# ProPrj_PCB.net
KiCad netlist of a schematic drawn in EasyEDA Pro
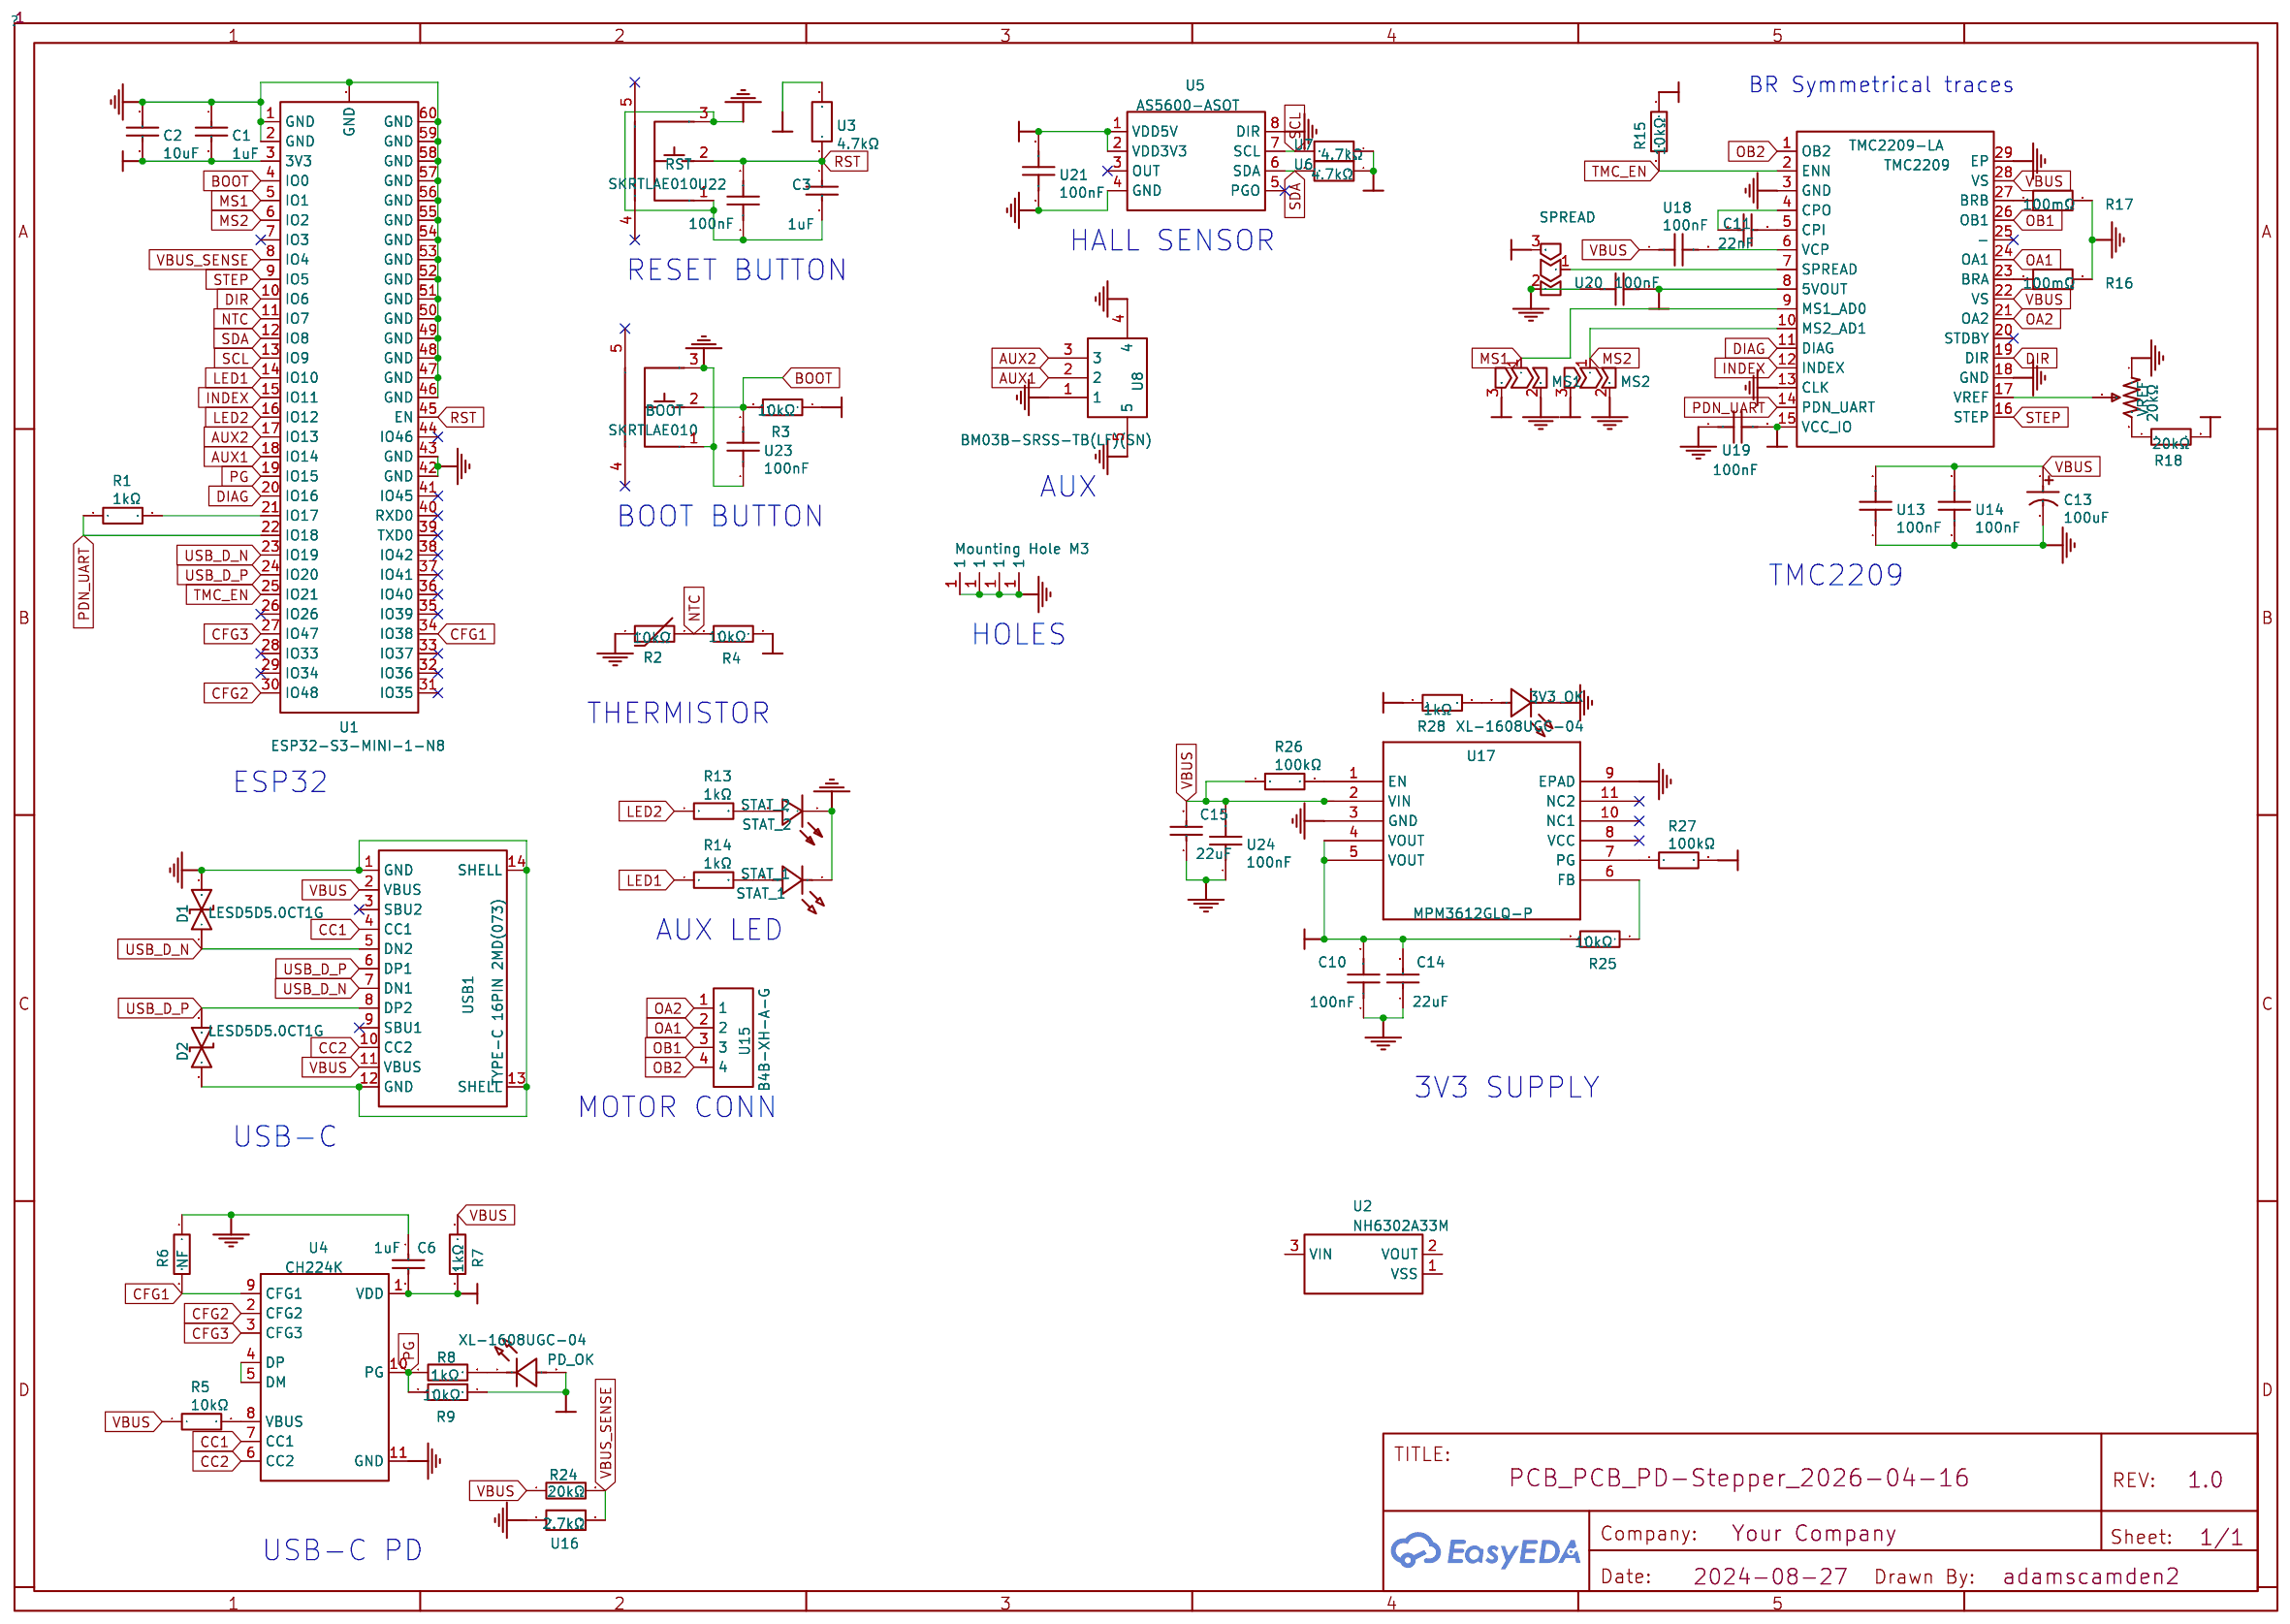
[diagram p0: schematic sheet]

(export (version "E")
  (design (tool "Eeschema 10.0.6"))
  (components
    (comp (ref "3V3_OK")
      (value "XL-1608UGC-04")
      (footprint "easyedapro:LED0603-RD_GREEN")
      (fields (field (name "Manufacturer") "XINGLIGHT(成兴光)") (field (name "Contributor") "lcsc"))
      (libsource (lib "") (part "XL-1608UGC-04_1"))
    )
    (comp (ref "BOOT")
      (value "SKRTLAE010")
      (footprint "easyedapro:KEY-SMD_SKRTLAE010")
      (fields (field (name "Manufacturer") "ALPSALPINE(阿尔卑斯阿尔派)"))
      (libsource (lib "easyedapro") (part "SKRTLAE010"))
    )
    (comp (ref "C1")
      (value "1uF")
      (footprint "easyedapro:C0402")
      (fields (field (name "Manufacturer Part") "0402B102K500NT") (field (name "Manufacturer") "FH(风华)"))
      (libsource (lib "easyedapro") (part "1uF"))
    )
    (comp (ref "C2")
      (value "10uF")
      (footprint "easyedapro:C0402")
      (fields (field (name "Manufacturer Part") "0402B102K500NT") (field (name "Manufacturer") "FH(风华)"))
      (libsource (lib "easyedapro") (part "10uF"))
    )
    (comp (ref "C3")
      (value "1uF")
      (footprint "easyedapro:C0402")
      (fields (field (name "Manufacturer Part") "0402B102K500NT") (field (name "Manufacturer") "FH(风华)"))
      (libsource (lib "easyedapro") (part "1uF"))
    )
    (comp (ref "C6")
      (value "1uF")
      (footprint "easyedapro:C0402")
      (fields (field (name "Manufacturer Part") "0402B102K500NT") (field (name "Manufacturer") "FH(风华)"))
      (libsource (lib "easyedapro") (part "1uF"))
    )
    (comp (ref "C10")
      (value "100nF")
      (footprint "easyedapro:C0402")
      (fields
        (field (name "Manufacturer Part") "CL05B104KO5NNNC")
        (field (name "Manufacturer") "SAMSUNG(三星)")
      )
      (libsource (lib "easyedapro") (part "100nF"))
    )
    (comp (ref "C11")
      (value "22nF")
      (footprint "easyedapro:C0805")
      (fields
        (field (name "Manufacturer Part") "CL21B223KBANNNC")
        (field (name "Manufacturer") "SAMSUNG(三星)")
      )
      (libsource (lib "easyedapro") (part "22nF"))
    )
    (comp (ref "C13")
      (value "100uF")
      (footprint "easyedapro:CAP-SMD_BD6.3-L6.6-W6.6-LS7.6-FD")
      (fields (field (name "Manufacturer Part") "RVT1V101M0607") (field (name "Manufacturer") "ROQANG(容强)"))
      (libsource (lib "easyedapro") (part "100uF"))
    )
    (comp (ref "C14")
      (value "22uF")
      (footprint "easyedapro:C0805")
      (fields (field (name "Manufacturer Part") "0805X226M250NT") (field (name "Manufacturer") "FH(风华)"))
      (libsource (lib "easyedapro") (part "22uF"))
    )
    (comp (ref "C15")
      (value "22uF")
      (footprint "easyedapro:C0805")
      (fields (field (name "Manufacturer Part") "0805X226M250NT") (field (name "Manufacturer") "FH(风华)"))
      (libsource (lib "easyedapro") (part "22uF"))
    )
    (comp (ref "D1")
      (value "LESD5D5.0CT1G")
      (footprint "easyedapro:SOD-523_L1.2-W0.8-LS1.6-BI")
      (fields (field (name "Manufacturer") "LRC(乐山无线电)") (field (name "Contributor") "LCSC"))
      (libsource (lib "easyedapro") (part "LESD5D5.0CT1G"))
    )
    (comp (ref "D2")
      (value "LESD5D5.0CT1G")
      (footprint "easyedapro:SOD-523_L1.2-W0.8-LS1.6-BI")
      (fields (field (name "Manufacturer") "LRC(乐山无线电)") (field (name "Contributor") "LCSC"))
      (libsource (lib "easyedapro") (part "LESD5D5.0CT1G"))
    )
    (comp (ref "MH1")
      (value "Mounting Hole M3")
      (footprint "easyedapro:MOUNTING HOLE M3")
      (fields (field (name "Contributor") "rexsell"))
      (libsource (lib "easyedapro") (part "Mounting Hole M3"))
    )
    (comp (ref "MH2")
      (value "Mounting Hole M3")
      (footprint "easyedapro:MOUNTING HOLE M3")
      (fields (field (name "Contributor") "rexsell"))
      (libsource (lib "easyedapro") (part "Mounting Hole M3"))
    )
    (comp (ref "MH3")
      (value "Mounting Hole M3")
      (footprint "easyedapro:MOUNTING HOLE M3")
      (fields (field (name "Contributor") "rexsell"))
      (libsource (lib "easyedapro") (part "Mounting Hole M3"))
    )
    (comp (ref "MH4")
      (value "Mounting Hole M3")
      (footprint "easyedapro:MOUNTING HOLE M3")
      (fields (field (name "Contributor") "rexsell"))
      (libsource (lib "easyedapro") (part "Mounting Hole M3"))
    )
    (comp (ref "MS1")
      (value "ms1")
      (footprint "easyedapro:SOLDERJUMPER3")
      (fields (field (name "Contributor") "un1tz3r0"))
      (libsource (lib "easyedapro") (part "ms1"))
    )
    (comp (ref "MS2")
      (value "MS2")
      (footprint "easyedapro:SOLDERJUMPER3")
      (fields (field (name "Contributor") "un1tz3r0"))
      (libsource (lib "easyedapro") (part "MS2"))
    )
    (comp (ref "PD_OK")
      (value "XL-1608UGC-04")
      (footprint "easyedapro:LED0603-RD_GREEN")
      (fields (field (name "Manufacturer") "XINGLIGHT(成兴光)") (field (name "Contributor") "lcsc"))
      (libsource (lib "easyedapro") (part "XL-1608UGC-04"))
    )
    (comp (ref "R1")
      (value "1kΩ")
      (footprint "easyedapro:R0402")
      (fields
        (field (name "Manufacturer Part") "0402WGF1001TCE")
        (field (name "Manufacturer") "UNI-ROYAL(厚声)")
      )
      (libsource (lib "easyedapro") (part "1kΩ"))
    )
    (comp (ref "R2")
      (value "10kΩ")
      (footprint "easyedapro:R0402")
      (fields (field (name "Manufacturer Part") "NTCG104BH103JT1") (field (name "Manufacturer") "TDK"))
      (libsource (lib "") (part "10kΩ_1"))
    )
    (comp (ref "R3")
      (value "10kΩ")
      (footprint "easyedapro:R0402")
      (fields
        (field (name "Manufacturer Part") "0402WGF1002TCE")
        (field (name "Manufacturer") "UNI-ROYAL(厚声)")
      )
      (libsource (lib "") (part "10kΩ_2"))
    )
    (comp (ref "R4")
      (value "10kΩ")
      (footprint "easyedapro:R0402")
      (fields
        (field (name "Manufacturer Part") "0402WGF1002TCE")
        (field (name "Manufacturer") "UNI-ROYAL(厚声)")
      )
      (libsource (lib "") (part "10kΩ_2"))
    )
    (comp (ref "R5")
      (value "10kΩ")
      (footprint "easyedapro:R0402")
      (fields
        (field (name "Manufacturer Part") "0402WGF1002TCE")
        (field (name "Manufacturer") "UNI-ROYAL(厚声)")
      )
      (libsource (lib "easyedapro") (part "10kΩ"))
    )
    (comp (ref "R6") (value "NF") (footprint "easyedapro:R0402") (libsource (lib "easyedapro") (part "NF")))
    (comp (ref "R7")
      (value "1kΩ")
      (footprint "easyedapro:R0402")
      (fields
        (field (name "Manufacturer Part") "0402WGF1001TCE")
        (field (name "Manufacturer") "UNI-ROYAL(厚声)")
      )
      (libsource (lib "") (part "1kΩ_1"))
    )
    (comp (ref "R8")
      (value "1kΩ")
      (footprint "easyedapro:R0402")
      (fields
        (field (name "Manufacturer Part") "0402WGF1001TCE")
        (field (name "Manufacturer") "UNI-ROYAL(厚声)")
      )
      (libsource (lib "easyedapro") (part "1kΩ"))
    )
    (comp (ref "R9")
      (value "10kΩ")
      (footprint "easyedapro:R0402")
      (fields
        (field (name "Manufacturer Part") "0402WGF1002TCE")
        (field (name "Manufacturer") "UNI-ROYAL(厚声)")
      )
      (libsource (lib "") (part "10kΩ_2"))
    )
    (comp (ref "R13")
      (value "1kΩ")
      (footprint "easyedapro:R0402")
      (fields
        (field (name "Manufacturer Part") "0402WGF1001TCE")
        (field (name "Manufacturer") "UNI-ROYAL(厚声)")
      )
      (libsource (lib "easyedapro") (part "1kΩ"))
    )
    (comp (ref "R14")
      (value "1kΩ")
      (footprint "easyedapro:R0402")
      (fields
        (field (name "Manufacturer Part") "0402WGF1001TCE")
        (field (name "Manufacturer") "UNI-ROYAL(厚声)")
      )
      (libsource (lib "easyedapro") (part "1kΩ"))
    )
    (comp (ref "R15")
      (value "10kΩ")
      (footprint "easyedapro:R0402")
      (fields
        (field (name "Manufacturer Part") "0402WGF1002TCE")
        (field (name "Manufacturer") "UNI-ROYAL(厚声)")
      )
      (libsource (lib "") (part "10kΩ_3"))
    )
    (comp (ref "R16")
      (value "100mΩ")
      (footprint "easyedapro:R2010")
      (fields
        (field (name "Manufacturer Part") "201007F100LT4E")
        (field (name "Manufacturer") "UNI-ROYAL(厚声)")
        (field (name "Contributor") "LCSC")
      )
      (libsource (lib "easyedapro") (part "100mΩ"))
    )
    (comp (ref "R17")
      (value "100mΩ")
      (footprint "easyedapro:R2010")
      (fields
        (field (name "Manufacturer Part") "201007F100LT4E")
        (field (name "Manufacturer") "UNI-ROYAL(厚声)")
        (field (name "Contributor") "LCSC")
      )
      (libsource (lib "easyedapro") (part "100mΩ"))
    )
    (comp (ref "R18")
      (value "20kΩ")
      (footprint "easyedapro:R0402")
      (fields
        (field (name "Manufacturer Part") "0402WGF2002TCE")
        (field (name "Manufacturer") "UNI-ROYAL(厚声)")
      )
      (libsource (lib "easyedapro") (part "20kΩ"))
    )
    (comp (ref "R24")
      (value "20kΩ")
      (footprint "easyedapro:R0402")
      (fields
        (field (name "Manufacturer Part") "0402WGF2002TCE")
        (field (name "Manufacturer") "UNI-ROYAL(厚声)")
      )
      (libsource (lib "easyedapro") (part "20kΩ"))
    )
    (comp (ref "R25")
      (value "10kΩ")
      (footprint "easyedapro:R0402")
      (fields
        (field (name "Manufacturer Part") "0402WGF1002TCE")
        (field (name "Manufacturer") "UNI-ROYAL(厚声)")
      )
      (libsource (lib "") (part "10kΩ_2"))
    )
    (comp (ref "R26")
      (value "100kΩ")
      (footprint "easyedapro:R0402")
      (fields
        (field (name "Manufacturer Part") "0402WGF1003TCE")
        (field (name "Manufacturer") "UNI-ROYAL(厚声)")
      )
      (libsource (lib "easyedapro") (part "100kΩ"))
    )
    (comp (ref "R27")
      (value "100kΩ")
      (footprint "easyedapro:R0402")
      (fields
        (field (name "Manufacturer Part") "0402WGF1003TCE")
        (field (name "Manufacturer") "UNI-ROYAL(厚声)")
      )
      (libsource (lib "easyedapro") (part "100kΩ"))
    )
    (comp (ref "R28")
      (value "1kΩ")
      (footprint "easyedapro:R0402")
      (fields
        (field (name "Manufacturer Part") "0402WGF1001TCE")
        (field (name "Manufacturer") "UNI-ROYAL(厚声)")
      )
      (libsource (lib "easyedapro") (part "1kΩ"))
    )
    (comp (ref "RST")
      (value "SKRTLAE010")
      (footprint "easyedapro:KEY-SMD_SKRTLAE010")
      (fields (field (name "Manufacturer") "ALPSALPINE(阿尔卑斯阿尔派)"))
      (libsource (lib "easyedapro") (part "SKRTLAE010"))
    )
    (comp (ref "SPREAD")
      (value "SPREAD")
      (footprint "easyedapro:SOLDERJUMPER3")
      (fields (field (name "Contributor") "un1tz3r0"))
      (libsource (lib "easyedapro") (part "SPREAD"))
    )
    (comp (ref "STAT_1")
      (value "STAT_1")
      (footprint "easyedapro:LED0603-RD_BLUE")
      (fields
        (field (name "Manufacturer Part") "XL-1608UBC-04")
        (field (name "Manufacturer") "XINGLIGHT(成兴光)")
        (field (name "Contributor") "LCSC")
      )
      (libsource (lib "easyedapro") (part "STAT_1"))
    )
    (comp (ref "STAT_2")
      (value "STAT_2")
      (footprint "easyedapro:LED0603-RD")
      (fields (field (name "Manufacturer Part") "KT-0603R") (field (name "Manufacturer") "KENTO"))
      (libsource (lib "easyedapro") (part "STAT_2"))
    )
    (comp (ref "TMC2209")
      (value "TMC2209-LA")
      (footprint "easyedapro:QFN-28_L5.0-W5.0-P0.50-BL-EP")
      (fields (field (name "Manufacturer") "TRINAMIC") (field (name "Contributor") "LCSC"))
      (libsource (lib "easyedapro") (part "TMC2209-LA"))
    )
    (comp (ref "U1")
      (value "ESP32-S3-MINI-1-N8")
      (footprint "easyedapro:BULETM-SMD_ESP32-S3-MINI-1-N8")
      (fields (field (name "Manufacturer") "ESPRESSIF(乐鑫)") (field (name "Contributor") "lcsc"))
      (libsource (lib "easyedapro") (part "ESP32-S3-MINI-1-N8"))
    )
    (comp (ref "U2")
      (value "NH6302A33M")
      (footprint "easyedapro:SOT-23-3_L2.9-W1.6-P1.90-LS2.8-BR")
      (fields (field (name "Manufacturer") "NH(纽航)") (field (name "Contributor") "lcsc"))
      (libsource (lib "easyedapro") (part "NH6302A33M"))
    )
    (comp (ref "U3")
      (value "4.7kΩ")
      (footprint "easyedapro:R0402")
      (fields
        (field (name "Manufacturer Part") "FRC0402J472 TS")
        (field (name "Manufacturer") "FOJAN(富捷)")
        (field (name "Contributor") "lcsc")
      )
      (libsource (lib "easyedapro") (part "4.7kΩ"))
    )
    (comp (ref "U4")
      (value "CH224K")
      (footprint "easyedapro:ESSOP-10_L4.9-W3.9-P1.0-LS6.0-TL-EP")
      (fields (field (name "Manufacturer") "WCH(南京沁恒)") (field (name "Contributor") "lcsc"))
      (libsource (lib "easyedapro") (part "CH224K"))
    )
    (comp (ref "U5")
      (value "AS5600-ASOT")
      (footprint "easyedapro:SOIC-8_L5.0-W4.0-P1.27-LS6.0-BL")
      (fields (field (name "Manufacturer") "ams(艾迈斯半导体)") (field (name "Contributor") "LCSC"))
      (libsource (lib "easyedapro") (part "AS5600-ASOT"))
    )
    (comp (ref "U6")
      (value "4.7kΩ")
      (footprint "easyedapro:R0402")
      (fields
        (field (name "Manufacturer Part") "FRC0402J472 TS")
        (field (name "Manufacturer") "FOJAN(富捷)")
        (field (name "Contributor") "lcsc")
      )
      (libsource (lib "") (part "4.7kΩ_1"))
    )
    (comp (ref "U7")
      (value "4.7kΩ")
      (footprint "easyedapro:R0402")
      (fields
        (field (name "Manufacturer Part") "FRC0402J472 TS")
        (field (name "Manufacturer") "FOJAN(富捷)")
        (field (name "Contributor") "lcsc")
      )
      (libsource (lib "") (part "4.7kΩ_1"))
    )
    (comp (ref "U8")
      (value "BM03B-SRSS-TB(LF)(SN)")
      (footprint "easyedapro:CONN-SMD-3P-P1.00_BM03B-SRSS-TB-LF-SN")
      (fields (field (name "Manufacturer") "JST") (field (name "Contributor") "LCSC"))
      (libsource (lib "easyedapro") (part "BM03B-SRSS-TB(LF)(SN)"))
    )
    (comp (ref "U13")
      (value "100nF")
      (footprint "easyedapro:C0402")
      (fields
        (field (name "Manufacturer Part") "CGA2B3X7R1V104KT0Y0F")
        (field (name "Manufacturer") "TDK")
        (field (name "Contributor") "lcsc")
      )
      (libsource (lib "easyedapro") (part "100nF"))
    )
    (comp (ref "U14")
      (value "100nF")
      (footprint "easyedapro:C0402")
      (fields
        (field (name "Manufacturer Part") "CGA2B3X7R1V104KT0Y0F")
        (field (name "Manufacturer") "TDK")
        (field (name "Contributor") "lcsc")
      )
      (libsource (lib "easyedapro") (part "100nF"))
    )
    (comp (ref "U15")
      (value "B4B-XH-A-G")
      (footprint "easyedapro:CONN-TH_B4B-XH-A-G")
      (fields (field (name "Manufacturer") "JST") (field (name "Contributor") "LCSC"))
      (libsource (lib "easyedapro") (part "B4B-XH-A-G"))
    )
    (comp (ref "U16")
      (value "2.7kΩ")
      (footprint "easyedapro:R0402")
      (fields
        (field (name "Manufacturer Part") "SCR0402J2K7")
        (field (name "Manufacturer") "VO(翔胜)")
        (field (name "Contributor") "lcsc")
      )
      (libsource (lib "easyedapro") (part "2.7kΩ"))
    )
    (comp (ref "U17")
      (value "MPM3612GLQ-P")
      (footprint "easyedapro:DFN-10_L3.0-W3.0-P0.65-BL-EP_MPM3612GLQ-Z")
      (fields (field (name "Contributor") "superslot"))
      (libsource (lib "easyedapro") (part "MPM3612GLQ-P"))
    )
    (comp (ref "U18")
      (value "100nF")
      (footprint "easyedapro:C0402")
      (fields
        (field (name "Manufacturer Part") "CGA2B3X7R1V104KT0Y0F")
        (field (name "Manufacturer") "TDK")
        (field (name "Contributor") "lcsc")
      )
      (libsource (lib "easyedapro") (part "100nF"))
    )
    (comp (ref "U19")
      (value "100nF")
      (footprint "easyedapro:C0402")
      (fields
        (field (name "Manufacturer Part") "CGA2B3X7R1V104KT0Y0F")
        (field (name "Manufacturer") "TDK")
        (field (name "Contributor") "lcsc")
      )
      (libsource (lib "easyedapro") (part "100nF"))
    )
    (comp (ref "U20")
      (value "100nF")
      (footprint "easyedapro:C0402")
      (fields
        (field (name "Manufacturer Part") "CGA2B3X7R1V104KT0Y0F")
        (field (name "Manufacturer") "TDK")
        (field (name "Contributor") "lcsc")
      )
      (libsource (lib "easyedapro") (part "100nF"))
    )
    (comp (ref "U21")
      (value "100nF")
      (footprint "easyedapro:C0402")
      (fields
        (field (name "Manufacturer Part") "CGA2B3X7R1V104KT0Y0F")
        (field (name "Manufacturer") "TDK")
        (field (name "Contributor") "lcsc")
      )
      (libsource (lib "easyedapro") (part "100nF"))
    )
    (comp (ref "U22")
      (value "100nF")
      (footprint "easyedapro:C0402")
      (fields
        (field (name "Manufacturer Part") "CGA2B3X7R1V104KT0Y0F")
        (field (name "Manufacturer") "TDK")
        (field (name "Contributor") "lcsc")
      )
      (libsource (lib "easyedapro") (part "100nF"))
    )
    (comp (ref "U23")
      (value "100nF")
      (footprint "easyedapro:C0402")
      (fields
        (field (name "Manufacturer Part") "CGA2B3X7R1V104KT0Y0F")
        (field (name "Manufacturer") "TDK")
        (field (name "Contributor") "lcsc")
      )
      (libsource (lib "easyedapro") (part "100nF"))
    )
    (comp (ref "U24")
      (value "100nF")
      (footprint "easyedapro:C0402")
      (fields
        (field (name "Manufacturer Part") "CGA2B3X7R1V104KT0Y0F")
        (field (name "Manufacturer") "TDK")
        (field (name "Contributor") "lcsc")
      )
      (libsource (lib "easyedapro") (part "100nF"))
    )
    (comp (ref "USB1")
      (value "TYPE-C 16PIN 2MD(073)")
      (footprint "easyedapro:USB-C-SMD_TYPE-C-6PIN-2MD-073")
      (fields (field (name "Manufacturer") "SHOU HAN(首韩)") (field (name "Contributor") "LCSC"))
      (libsource (lib "easyedapro") (part "TYPE-C 16PIN 2MD(073)"))
    )
    (comp (ref "VREF")
      (value "20kΩ")
      (footprint "easyedapro:RES-ADJ-SMD_TC33X-2-104E")
      (fields
        (field (name "Manufacturer Part") "TC33X-2-203E")
        (field (name "Manufacturer") "BOURNS")
        (field (name "Contributor") "lcsc")
      )
      (libsource (lib "") (part "20kΩ_1"))
    )
  )
  (nets
    (net (code "1") (name "+5V") (class "Default")
      (node (ref "R18") (pin "2") (pinfunction "2_2") (pintype "input"))
      (node (ref "TMC2209") (pin "8") (pinfunction "5VOUT_8") (pintype "unspecified"))
      (node (ref "U20") (pin "1") (pinfunction "1_1") (pintype "unspecified"))
    )
    (net (code "2") (name "3V3") (class "Default")
      (node (ref "C1") (pin "2") (pinfunction "2_2") (pintype "input"))
      (node (ref "C10") (pin "2") (pinfunction "2_2") (pintype "unspecified"))
      (node (ref "C14") (pin "2") (pinfunction "2_2") (pintype "input"))
      (node (ref "C2") (pin "1") (pinfunction "1_1") (pintype "input"))
      (node (ref "C6") (pin "2") (pinfunction "2_2") (pintype "input"))
      (node (ref "MS1") (pin "3") (pinfunction "3_3") (pintype "unspecified"))
      (node (ref "MS2") (pin "3") (pinfunction "3_3") (pintype "unspecified"))
      (node (ref "PD_OK") (pin "2") (pinfunction "A_2") (pintype "unspecified"))
      (node (ref "R15") (pin "1") (pinfunction "1_1") (pintype "input"))
      (node (ref "R25") (pin "2") (pinfunction "2_2") (pintype "input"))
      (node (ref "R27") (pin "2") (pinfunction "2_2") (pintype "input"))
      (node (ref "R28") (pin "1") (pinfunction "1_1") (pintype "input"))
      (node (ref "R3") (pin "1") (pinfunction "1_1") (pintype "input"))
      (node (ref "R4") (pin "1") (pinfunction "1_1") (pintype "input"))
      (node (ref "R7") (pin "2") (pinfunction "2_2") (pintype "input"))
      (node (ref "R9") (pin "1") (pinfunction "1_1") (pintype "input"))
      (node (ref "SPREAD") (pin "3") (pinfunction "3_3") (pintype "unspecified"))
      (node (ref "TMC2209") (pin "15") (pinfunction "VCC_IO_15") (pintype "unspecified"))
      (node (ref "U1") (pin "3") (pinfunction "3V3_3") (pintype "unspecified"))
      (node (ref "U17") (pin "4") (pinfunction "VOUT_4") (pintype "bidirectional"))
      (node (ref "U17") (pin "5") (pinfunction "VOUT_5") (pintype "bidirectional"))
      (node (ref "U19") (pin "2") (pinfunction "2_2") (pintype "unspecified"))
      (node (ref "U21") (pin "2") (pinfunction "2_2") (pintype "unspecified"))
      (node (ref "U3") (pin "2") (pinfunction "2_2") (pintype "unspecified"))
      (node (ref "U4") (pin "1") (pinfunction "VDD_1") (pintype "unspecified"))
      (node (ref "U5") (pin "1") (pinfunction "VDD5V_1") (pintype "unspecified"))
      (node (ref "U5") (pin "2") (pinfunction "VDD3V3_2") (pintype "unspecified"))
      (node (ref "U6") (pin "1") (pinfunction "1_1") (pintype "unspecified"))
      (node (ref "U7") (pin "1") (pinfunction "1_1") (pintype "unspecified"))
    )
    (net (code "3") (name "AUX1") (class "Default")
      (node (ref "U1") (pin "18") (pinfunction "IO14_18") (pintype "unspecified"))
      (node (ref "U8") (pin "2") (pinfunction "2_2") (pintype "unspecified"))
    )
    (net (code "4") (name "AUX2") (class "Default")
      (node (ref "U1") (pin "17") (pinfunction "IO13_17") (pintype "unspecified"))
      (node (ref "U8") (pin "3") (pinfunction "3_3") (pintype "unspecified"))
    )
    (net (code "5") (name "BOOT") (class "Default")
      (node (ref "BOOT") (pin "2") (pinfunction "2_2") (pintype "input"))
      (node (ref "R3") (pin "2") (pinfunction "2_2") (pintype "input"))
      (node (ref "U1") (pin "4") (pinfunction "IO0_4") (pintype "unspecified"))
      (node (ref "U23") (pin "2") (pinfunction "2_2") (pintype "unspecified"))
    )
    (net (code "6") (name "CC1") (class "Default")
      (node (ref "U4") (pin "7") (pinfunction "CC1_7") (pintype "unspecified"))
      (node (ref "USB1") (pin "4") (pinfunction "CC1_4") (pintype "unspecified"))
    )
    (net (code "7") (name "CC2") (class "Default")
      (node (ref "U4") (pin "6") (pinfunction "CC2_6") (pintype "unspecified"))
      (node (ref "USB1") (pin "10") (pinfunction "CC2_10") (pintype "unspecified"))
    )
    (net (code "8") (name "CFG1") (class "Default")
      (node (ref "R6") (pin "2") (pinfunction "2_2") (pintype "input"))
      (node (ref "U1") (pin "34") (pinfunction "IO38_34") (pintype "unspecified"))
      (node (ref "U4") (pin "9") (pinfunction "CFG1_9") (pintype "unspecified"))
    )
    (net (code "9") (name "CFG2") (class "Default")
      (node (ref "U1") (pin "30") (pinfunction "IO48_30") (pintype "unspecified"))
      (node (ref "U4") (pin "2") (pinfunction "CFG2_2") (pintype "unspecified"))
    )
    (net (code "10") (name "CFG3") (class "Default")
      (node (ref "U1") (pin "27") (pinfunction "IO47_27") (pintype "unspecified"))
      (node (ref "U4") (pin "3") (pinfunction "CFG3_3") (pintype "unspecified"))
    )
    (net (code "11") (name "DIAG") (class "Default")
      (node (ref "TMC2209") (pin "11") (pinfunction "DIAG_11") (pintype "unspecified"))
      (node (ref "U1") (pin "20") (pinfunction "IO16_20") (pintype "unspecified"))
    )
    (net (code "12") (name "DIR") (class "Default")
      (node (ref "TMC2209") (pin "19") (pinfunction "DIR_19") (pintype "unspecified"))
      (node (ref "U1") (pin "10") (pinfunction "IO6_10") (pintype "unspecified"))
    )
    (net (code "13") (name "GND") (class "Default")
      (node (ref "3V3_OK") (pin "1") (pinfunction "K_1") (pintype "unspecified"))
      (node (ref "BOOT") (pin "1") (pinfunction "1_1") (pintype "input"))
      (node (ref "BOOT") (pin "3") (pinfunction "3_3") (pintype "input"))
      (node (ref "C1") (pin "1") (pinfunction "1_1") (pintype "input"))
      (node (ref "C10") (pin "1") (pinfunction "1_1") (pintype "unspecified"))
      (node (ref "C13") (pin "2") (pinfunction "2_2") (pintype "input"))
      (node (ref "C14") (pin "1") (pinfunction "1_1") (pintype "input"))
      (node (ref "C15") (pin "1") (pinfunction "1_1") (pintype "input"))
      (node (ref "C2") (pin "2") (pinfunction "2_2") (pintype "input"))
      (node (ref "C3") (pin "2") (pinfunction "2_2") (pintype "input"))
      (node (ref "C6") (pin "1") (pinfunction "1_1") (pintype "input"))
      (node (ref "D1") (pin "2") (pinfunction "2_2") (pintype "unspecified"))
      (node (ref "D2") (pin "1") (pinfunction "1_1") (pintype "unspecified"))
      (node (ref "MH1") (pin "1") (pinfunction "1_1") (pintype "unspecified"))
      (node (ref "MH2") (pin "1") (pinfunction "1_1") (pintype "unspecified"))
      (node (ref "MH3") (pin "1") (pinfunction "1_1") (pintype "unspecified"))
      (node (ref "MH4") (pin "1") (pinfunction "1_1") (pintype "unspecified"))
      (node (ref "MS1") (pin "2") (pinfunction "2_2") (pintype "unspecified"))
      (node (ref "MS2") (pin "2") (pinfunction "2_2") (pintype "unspecified"))
      (node (ref "R16") (pin "2") (pinfunction "2_2") (pintype "unspecified"))
      (node (ref "R17") (pin "2") (pinfunction "2_2") (pintype "unspecified"))
      (node (ref "R2") (pin "1") (pinfunction "1_1") (pintype "input"))
      (node (ref "R6") (pin "1") (pinfunction "1_1") (pintype "input"))
      (node (ref "RST") (pin "1") (pinfunction "1_1") (pintype "input"))
      (node (ref "RST") (pin "3") (pinfunction "3_3") (pintype "input"))
      (node (ref "SPREAD") (pin "2") (pinfunction "2_2") (pintype "unspecified"))
      (node (ref "STAT_1") (pin "1") (pinfunction "K_1") (pintype "unspecified"))
      (node (ref "STAT_2") (pin "1") (pinfunction "K_1") (pintype "unspecified"))
      (node (ref "TMC2209") (pin "13") (pinfunction "CLK_13") (pintype "unspecified"))
      (node (ref "TMC2209") (pin "18") (pinfunction "GND_18") (pintype "unspecified"))
      (node (ref "TMC2209") (pin "29") (pinfunction "EP_29") (pintype "unspecified"))
      (node (ref "TMC2209") (pin "3") (pinfunction "GND_3") (pintype "unspecified"))
      (node (ref "U1") (pin "1") (pinfunction "GND_1") (pintype "unspecified"))
      (node (ref "U1") (pin "2") (pinfunction "GND_2") (pintype "unspecified"))
      (node (ref "U1") (pin "42") (pinfunction "GND_42") (pintype "unspecified"))
      (node (ref "U1") (pin "43") (pinfunction "GND_43") (pintype "unspecified"))
      (node (ref "U1") (pin "46") (pinfunction "GND_46") (pintype "unspecified"))
      (node (ref "U1") (pin "47") (pinfunction "GND_47") (pintype "unspecified"))
      (node (ref "U1") (pin "48") (pinfunction "GND_48") (pintype "unspecified"))
      (node (ref "U1") (pin "49") (pinfunction "GND_49") (pintype "unspecified"))
      (node (ref "U1") (pin "50") (pinfunction "GND_50") (pintype "unspecified"))
      (node (ref "U1") (pin "51") (pinfunction "GND_51") (pintype "unspecified"))
      (node (ref "U1") (pin "52") (pinfunction "GND_52") (pintype "unspecified"))
      (node (ref "U1") (pin "53") (pinfunction "GND_53") (pintype "unspecified"))
      (node (ref "U1") (pin "54") (pinfunction "GND_54") (pintype "unspecified"))
      (node (ref "U1") (pin "55") (pinfunction "GND_55") (pintype "unspecified"))
      (node (ref "U1") (pin "56") (pinfunction "GND_56") (pintype "unspecified"))
      (node (ref "U1") (pin "57") (pinfunction "GND_57") (pintype "unspecified"))
      (node (ref "U1") (pin "58") (pinfunction "GND_58") (pintype "unspecified"))
      (node (ref "U1") (pin "59") (pinfunction "GND_59") (pintype "unspecified"))
      (node (ref "U1") (pin "60") (pinfunction "GND_60") (pintype "unspecified"))
      (node (ref "U1") (pin "GND") (pinfunction "GND_GND") (pintype "unspecified"))
      (node (ref "U13") (pin "1") (pinfunction "1_1") (pintype "unspecified"))
      (node (ref "U14") (pin "1") (pinfunction "1_1") (pintype "unspecified"))
      (node (ref "U16") (pin "1") (pinfunction "1_1") (pintype "unspecified"))
      (node (ref "U17") (pin "3") (pinfunction "GND_3") (pintype "bidirectional"))
      (node (ref "U17") (pin "9") (pinfunction "EPAD_9") (pintype "bidirectional"))
      (node (ref "U19") (pin "1") (pinfunction "1_1") (pintype "unspecified"))
      (node (ref "U20") (pin "2") (pinfunction "2_2") (pintype "unspecified"))
      (node (ref "U21") (pin "1") (pinfunction "1_1") (pintype "unspecified"))
      (node (ref "U22") (pin "1") (pinfunction "1_1") (pintype "unspecified"))
      (node (ref "U23") (pin "1") (pinfunction "1_1") (pintype "unspecified"))
      (node (ref "U24") (pin "1") (pinfunction "1_1") (pintype "unspecified"))
      (node (ref "U4") (pin "11") (pinfunction "GND_11") (pintype "unspecified"))
      (node (ref "U5") (pin "4") (pinfunction "GND_4") (pintype "unspecified"))
      (node (ref "U5") (pin "8") (pinfunction "DIR_8") (pintype "unspecified"))
      (node (ref "U8") (pin "1") (pinfunction "1_1") (pintype "unspecified"))
      (node (ref "U8") (pin "4") (pinfunction "4_4") (pintype "unspecified"))
      (node (ref "U8") (pin "5") (pinfunction "5_5") (pintype "unspecified"))
      (node (ref "USB1") (pin "1") (pinfunction "GND_1") (pintype "unspecified"))
      (node (ref "USB1") (pin "12") (pinfunction "GND_12") (pintype "unspecified"))
      (node (ref "USB1") (pin "13") (pinfunction "SHELL_13") (pintype "unspecified"))
      (node (ref "USB1") (pin "14") (pinfunction "SHELL_14") (pintype "unspecified"))
      (node (ref "VREF") (pin "1") (pinfunction "1_1") (pintype "unspecified"))
    )
    (net (code "14") (name "INDEX") (class "Default")
      (node (ref "TMC2209") (pin "12") (pinfunction "INDEX_12") (pintype "unspecified"))
      (node (ref "U1") (pin "15") (pinfunction "IO11_15") (pintype "unspecified"))
    )
    (net (code "15") (name "LED1") (class "Default")
      (node (ref "R14") (pin "1") (pinfunction "1_1") (pintype "input"))
      (node (ref "U1") (pin "14") (pinfunction "IO10_14") (pintype "unspecified"))
    )
    (net (code "16") (name "LED2") (class "Default")
      (node (ref "R13") (pin "1") (pinfunction "1_1") (pintype "input"))
      (node (ref "U1") (pin "16") (pinfunction "IO12_16") (pintype "unspecified"))
    )
    (net (code "17") (name "MS1") (class "Default")
      (node (ref "MS1") (pin "1") (pinfunction "1_1") (pintype "unspecified"))
      (node (ref "TMC2209") (pin "9") (pinfunction "MS1_AD0_9") (pintype "unspecified"))
      (node (ref "U1") (pin "5") (pinfunction "IO1_5") (pintype "unspecified"))
    )
    (net (code "18") (name "MS2") (class "Default")
      (node (ref "MS2") (pin "1") (pinfunction "1_1") (pintype "unspecified"))
      (node (ref "TMC2209") (pin "10") (pinfunction "MS2_AD1_10") (pintype "unspecified"))
      (node (ref "U1") (pin "6") (pinfunction "IO2_6") (pintype "unspecified"))
    )
    (net (code "19") (name "NTC") (class "Default")
      (node (ref "R2") (pin "2") (pinfunction "2_2") (pintype "input"))
      (node (ref "R4") (pin "2") (pinfunction "2_2") (pintype "input"))
      (node (ref "U1") (pin "11") (pinfunction "IO7_11") (pintype "unspecified"))
    )
    (net (code "20") (name "Net-(3V3_OK-A)") (class "Default")
      (node (ref "3V3_OK") (pin "2") (pinfunction "A_2") (pintype "unspecified"))
      (node (ref "R28") (pin "2") (pinfunction "2_2") (pintype "input"))
    )
    (net (code "21") (name "Net-(PD_OK-K)") (class "Default")
      (node (ref "PD_OK") (pin "1") (pinfunction "K_1") (pintype "unspecified"))
      (node (ref "R8") (pin "2") (pinfunction "2_2") (pintype "input"))
    )
    (net (code "22") (name "Net-(R18-Pad1)") (class "Default")
      (node (ref "R18") (pin "1") (pinfunction "1_1") (pintype "input"))
      (node (ref "VREF") (pin "3") (pinfunction "3_3") (pintype "unspecified"))
    )
    (net (code "23") (name "Net-(STAT_1-A)") (class "Default")
      (node (ref "R14") (pin "2") (pinfunction "2_2") (pintype "input"))
      (node (ref "STAT_1") (pin "2") (pinfunction "A_2") (pintype "unspecified"))
    )
    (net (code "24") (name "Net-(STAT_2-A)") (class "Default")
      (node (ref "R13") (pin "2") (pinfunction "2_2") (pintype "input"))
      (node (ref "STAT_2") (pin "2") (pinfunction "A_2") (pintype "unspecified"))
    )
    (net (code "25") (name "Net-(TMC2209-BRA)") (class "Default")
      (node (ref "R16") (pin "1") (pinfunction "1_1") (pintype "unspecified"))
      (node (ref "TMC2209") (pin "23") (pinfunction "BRA_23") (pintype "unspecified"))
    )
    (net (code "26") (name "Net-(TMC2209-BRB)") (class "Default")
      (node (ref "R17") (pin "1") (pinfunction "1_1") (pintype "unspecified"))
      (node (ref "TMC2209") (pin "27") (pinfunction "BRB_27") (pintype "unspecified"))
    )
    (net (code "27") (name "Net-(TMC2209-CPI)") (class "Default")
      (node (ref "C11") (pin "2") (pinfunction "2_2") (pintype "input"))
      (node (ref "TMC2209") (pin "5") (pinfunction "CPI_5") (pintype "unspecified"))
    )
    (net (code "28") (name "Net-(TMC2209-CPO)") (class "Default")
      (node (ref "C11") (pin "1") (pinfunction "1_1") (pintype "input"))
      (node (ref "TMC2209") (pin "4") (pinfunction "CPO_4") (pintype "unspecified"))
    )
    (net (code "29") (name "Net-(TMC2209-SPREAD)") (class "Default")
      (node (ref "SPREAD") (pin "1") (pinfunction "1_1") (pintype "unspecified"))
      (node (ref "TMC2209") (pin "7") (pinfunction "SPREAD_7") (pintype "unspecified"))
    )
    (net (code "30") (name "Net-(TMC2209-VCP)") (class "Default")
      (node (ref "TMC2209") (pin "6") (pinfunction "VCP_6") (pintype "unspecified"))
      (node (ref "U18") (pin "2") (pinfunction "2_2") (pintype "unspecified"))
    )
    (net (code "31") (name "Net-(TMC2209-VREF)") (class "Default")
      (node (ref "TMC2209") (pin "17") (pinfunction "VREF_17") (pintype "unspecified"))
      (node (ref "VREF") (pin "2") (pinfunction "2_2") (pintype "unspecified"))
    )
    (net (code "32") (name "Net-(U1-IO17)") (class "Default")
      (node (ref "R1") (pin "2") (pinfunction "2_2") (pintype "input"))
      (node (ref "U1") (pin "21") (pinfunction "IO17_21") (pintype "unspecified"))
    )
    (net (code "33") (name "Net-(U4-DM)") (class "Default")
      (node (ref "U4") (pin "4") (pinfunction "DP_4") (pintype "unspecified"))
      (node (ref "U4") (pin "5") (pinfunction "DM_5") (pintype "unspecified"))
    )
    (net (code "34") (name "Net-(U4-VBUS)") (class "Default")
      (node (ref "R5") (pin "2") (pinfunction "2_2") (pintype "input"))
      (node (ref "U4") (pin "8") (pinfunction "VBUS_8") (pintype "unspecified"))
    )
    (net (code "35") (name "Net-(U17-EN)") (class "Default")
      (node (ref "R26") (pin "2") (pinfunction "2_2") (pintype "input"))
      (node (ref "U17") (pin "1") (pinfunction "EN_1") (pintype "unspecified"))
    )
    (net (code "36") (name "Net-(U17-FB)") (class "Default")
      (node (ref "R25") (pin "1") (pinfunction "1_1") (pintype "input"))
      (node (ref "U17") (pin "6") (pinfunction "FB_6") (pintype "unspecified"))
    )
    (net (code "37") (name "Net-(U17-PG)") (class "Default")
      (node (ref "R27") (pin "1") (pinfunction "1_1") (pintype "input"))
      (node (ref "U17") (pin "7") (pinfunction "PG_7") (pintype "output"))
    )
    (net (code "38") (name "OA1") (class "Default")
      (node (ref "TMC2209") (pin "24") (pinfunction "OA1_24") (pintype "unspecified"))
      (node (ref "U15") (pin "2") (pinfunction "2_2") (pintype "unspecified"))
    )
    (net (code "39") (name "OA2") (class "Default")
      (node (ref "TMC2209") (pin "21") (pinfunction "OA2_21") (pintype "unspecified"))
      (node (ref "U15") (pin "1") (pinfunction "1_1") (pintype "unspecified"))
    )
    (net (code "40") (name "OB1") (class "Default")
      (node (ref "TMC2209") (pin "26") (pinfunction "OB1_26") (pintype "unspecified"))
      (node (ref "U15") (pin "3") (pinfunction "3_3") (pintype "unspecified"))
    )
    (net (code "41") (name "OB2") (class "Default")
      (node (ref "TMC2209") (pin "1") (pinfunction "OB2_1") (pintype "unspecified"))
      (node (ref "U15") (pin "4") (pinfunction "4_4") (pintype "unspecified"))
    )
    (net (code "42") (name "PDN_UART") (class "Default")
      (node (ref "R1") (pin "1") (pinfunction "1_1") (pintype "input"))
      (node (ref "TMC2209") (pin "14") (pinfunction "PDN_UART_14") (pintype "unspecified"))
      (node (ref "U1") (pin "22") (pinfunction "IO18_22") (pintype "unspecified"))
    )
    (net (code "43") (name "PG") (class "Default")
      (node (ref "R8") (pin "1") (pinfunction "1_1") (pintype "input"))
      (node (ref "R9") (pin "2") (pinfunction "2_2") (pintype "input"))
      (node (ref "U1") (pin "19") (pinfunction "IO15_19") (pintype "unspecified"))
      (node (ref "U4") (pin "10") (pinfunction "PG_10") (pintype "unspecified"))
    )
    (net (code "44") (name "RST") (class "Default")
      (node (ref "C3") (pin "1") (pinfunction "1_1") (pintype "input"))
      (node (ref "RST") (pin "2") (pinfunction "2_2") (pintype "input"))
      (node (ref "U1") (pin "45") (pinfunction "EN_45") (pintype "unspecified"))
      (node (ref "U22") (pin "2") (pinfunction "2_2") (pintype "unspecified"))
      (node (ref "U3") (pin "1") (pinfunction "1_1") (pintype "unspecified"))
    )
    (net (code "45") (name "SCL") (class "Default")
      (node (ref "U1") (pin "13") (pinfunction "IO9_13") (pintype "unspecified"))
      (node (ref "U5") (pin "7") (pinfunction "SCL_7") (pintype "unspecified"))
      (node (ref "U7") (pin "2") (pinfunction "2_2") (pintype "unspecified"))
    )
    (net (code "46") (name "SDA") (class "Default")
      (node (ref "U1") (pin "12") (pinfunction "IO8_12") (pintype "unspecified"))
      (node (ref "U5") (pin "6") (pinfunction "SDA_6") (pintype "unspecified"))
      (node (ref "U6") (pin "2") (pinfunction "2_2") (pintype "unspecified"))
    )
    (net (code "47") (name "STEP") (class "Default")
      (node (ref "TMC2209") (pin "16") (pinfunction "STEP_16") (pintype "unspecified"))
      (node (ref "U1") (pin "9") (pinfunction "IO5_9") (pintype "unspecified"))
    )
    (net (code "48") (name "TMC_EN") (class "Default")
      (node (ref "R15") (pin "2") (pinfunction "2_2") (pintype "input"))
      (node (ref "TMC2209") (pin "2") (pinfunction "ENN_2") (pintype "unspecified"))
      (node (ref "U1") (pin "25") (pinfunction "IO21_25") (pintype "unspecified"))
    )
    (net (code "49") (name "USB_D_N") (class "Default")
      (node (ref "D1") (pin "1") (pinfunction "1_1") (pintype "unspecified"))
      (node (ref "U1") (pin "23") (pinfunction "IO19_23") (pintype "unspecified"))
      (node (ref "USB1") (pin "5") (pinfunction "DN2_5") (pintype "unspecified"))
      (node (ref "USB1") (pin "7") (pinfunction "DN1_7") (pintype "unspecified"))
    )
    (net (code "50") (name "USB_D_P") (class "Default")
      (node (ref "D2") (pin "2") (pinfunction "2_2") (pintype "unspecified"))
      (node (ref "U1") (pin "24") (pinfunction "IO20_24") (pintype "unspecified"))
      (node (ref "USB1") (pin "6") (pinfunction "DP1_6") (pintype "unspecified"))
      (node (ref "USB1") (pin "8") (pinfunction "DP2_8") (pintype "unspecified"))
    )
    (net (code "51") (name "VBUS") (class "Default")
      (node (ref "C13") (pin "1") (pinfunction "1_1") (pintype "input"))
      (node (ref "C15") (pin "2") (pinfunction "2_2") (pintype "input"))
      (node (ref "R24") (pin "1") (pinfunction "1_1") (pintype "input"))
      (node (ref "R26") (pin "1") (pinfunction "1_1") (pintype "input"))
      (node (ref "R5") (pin "1") (pinfunction "1_1") (pintype "input"))
      (node (ref "R7") (pin "1") (pinfunction "1_1") (pintype "input"))
      (node (ref "TMC2209") (pin "22") (pinfunction "VS_22") (pintype "unspecified"))
      (node (ref "TMC2209") (pin "28") (pinfunction "VS_28") (pintype "unspecified"))
      (node (ref "U13") (pin "2") (pinfunction "2_2") (pintype "unspecified"))
      (node (ref "U14") (pin "2") (pinfunction "2_2") (pintype "unspecified"))
      (node (ref "U17") (pin "2") (pinfunction "VIN_2") (pintype "bidirectional"))
      (node (ref "U18") (pin "1") (pinfunction "1_1") (pintype "unspecified"))
      (node (ref "U24") (pin "2") (pinfunction "2_2") (pintype "unspecified"))
      (node (ref "USB1") (pin "11") (pinfunction "VBUS_11") (pintype "unspecified"))
      (node (ref "USB1") (pin "2") (pinfunction "VBUS_2") (pintype "unspecified"))
    )
    (net (code "52") (name "VBUS_SENSE") (class "Default")
      (node (ref "R24") (pin "2") (pinfunction "2_2") (pintype "input"))
      (node (ref "U1") (pin "8") (pinfunction "IO4_8") (pintype "unspecified"))
      (node (ref "U16") (pin "2") (pinfunction "2_2") (pintype "unspecified"))
    )
    (net (code "53") (name "unconnected-(BOOT-Pad4)") (class "Default")
      (node (ref "BOOT") (pin "4") (pinfunction "4_4") (pintype "unspecified+no_connect"))
    )
    (net (code "54") (name "unconnected-(BOOT-Pad5)") (class "Default")
      (node (ref "BOOT") (pin "5") (pinfunction "5_5") (pintype "unspecified+no_connect"))
    )
    (net (code "55") (name "unconnected-(RST-Pad4)") (class "Default")
      (node (ref "RST") (pin "4") (pinfunction "4_4") (pintype "unspecified+no_connect"))
    )
    (net (code "56") (name "unconnected-(RST-Pad5)") (class "Default")
      (node (ref "RST") (pin "5") (pinfunction "5_5") (pintype "unspecified+no_connect"))
    )
    (net (code "57") (name "unconnected-(TMC2209---Pad25)") (class "Default")
      (node (ref "TMC2209") (pin "25") (pinfunction "-_25") (pintype "unspecified+no_connect"))
    )
    (net (code "58") (name "unconnected-(TMC2209-STDBY-Pad20)") (class "Default")
      (node (ref "TMC2209") (pin "20") (pinfunction "STDBY_20") (pintype "unspecified+no_connect"))
    )
    (net (code "59") (name "unconnected-(U1-IO3-Pad7)") (class "Default")
      (node (ref "U1") (pin "7") (pinfunction "IO3_7") (pintype "unspecified+no_connect"))
    )
    (net (code "60") (name "unconnected-(U1-IO26-Pad26)") (class "Default")
      (node (ref "U1") (pin "26") (pinfunction "IO26_26") (pintype "unspecified+no_connect"))
    )
    (net (code "61") (name "unconnected-(U1-IO33-Pad28)") (class "Default")
      (node (ref "U1") (pin "28") (pinfunction "IO33_28") (pintype "unspecified+no_connect"))
    )
    (net (code "62") (name "unconnected-(U1-IO34-Pad29)") (class "Default")
      (node (ref "U1") (pin "29") (pinfunction "IO34_29") (pintype "unspecified+no_connect"))
    )
    (net (code "63") (name "unconnected-(U1-IO35-Pad31)") (class "Default")
      (node (ref "U1") (pin "31") (pinfunction "IO35_31") (pintype "unspecified+no_connect"))
    )
    (net (code "64") (name "unconnected-(U1-IO36-Pad32)") (class "Default")
      (node (ref "U1") (pin "32") (pinfunction "IO36_32") (pintype "unspecified+no_connect"))
    )
    (net (code "65") (name "unconnected-(U1-IO37-Pad33)") (class "Default")
      (node (ref "U1") (pin "33") (pinfunction "IO37_33") (pintype "unspecified+no_connect"))
    )
    (net (code "66") (name "unconnected-(U1-IO39-Pad35)") (class "Default")
      (node (ref "U1") (pin "35") (pinfunction "IO39_35") (pintype "unspecified+no_connect"))
    )
    (net (code "67") (name "unconnected-(U1-IO40-Pad36)") (class "Default")
      (node (ref "U1") (pin "36") (pinfunction "IO40_36") (pintype "unspecified+no_connect"))
    )
    (net (code "68") (name "unconnected-(U1-IO41-Pad37)") (class "Default")
      (node (ref "U1") (pin "37") (pinfunction "IO41_37") (pintype "unspecified+no_connect"))
    )
    (net (code "69") (name "unconnected-(U1-IO42-Pad38)") (class "Default")
      (node (ref "U1") (pin "38") (pinfunction "IO42_38") (pintype "unspecified+no_connect"))
    )
    (net (code "70") (name "unconnected-(U1-IO45-Pad41)") (class "Default")
      (node (ref "U1") (pin "41") (pinfunction "IO45_41") (pintype "unspecified+no_connect"))
    )
    (net (code "71") (name "unconnected-(U1-IO46-Pad44)") (class "Default")
      (node (ref "U1") (pin "44") (pinfunction "IO46_44") (pintype "unspecified+no_connect"))
    )
    (net (code "72") (name "unconnected-(U1-RXD0-Pad40)") (class "Default")
      (node (ref "U1") (pin "40") (pinfunction "RXD0_40") (pintype "unspecified+no_connect"))
    )
    (net (code "73") (name "unconnected-(U1-TXD0-Pad39)") (class "Default")
      (node (ref "U1") (pin "39") (pinfunction "TXD0_39") (pintype "unspecified+no_connect"))
    )
    (net (code "74") (name "unconnected-(U2-VIN-Pad3)") (class "Default")
      (node (ref "U2") (pin "3") (pinfunction "VIN_3") (pintype "unspecified"))
    )
    (net (code "75") (name "unconnected-(U2-VOUT-Pad2)") (class "Default")
      (node (ref "U2") (pin "2") (pinfunction "VOUT_2") (pintype "unspecified"))
    )
    (net (code "76") (name "unconnected-(U2-VSS-Pad1)") (class "Default")
      (node (ref "U2") (pin "1") (pinfunction "VSS_1") (pintype "unspecified"))
    )
    (net (code "77") (name "unconnected-(U5-OUT-Pad3)") (class "Default")
      (node (ref "U5") (pin "3") (pinfunction "OUT_3") (pintype "unspecified+no_connect"))
    )
    (net (code "78") (name "unconnected-(U5-PGO-Pad5)") (class "Default")
      (node (ref "U5") (pin "5") (pinfunction "PGO_5") (pintype "unspecified+no_connect"))
    )
    (net (code "79") (name "unconnected-(U17-NC1-Pad10)") (class "Default")
      (node (ref "U17") (pin "10") (pinfunction "NC1_10") (pintype "bidirectional+no_connect"))
    )
    (net (code "80") (name "unconnected-(U17-NC2-Pad11)") (class "Default")
      (node (ref "U17") (pin "11") (pinfunction "NC2_11") (pintype "bidirectional+no_connect"))
    )
    (net (code "81") (name "unconnected-(U17-VCC-Pad8)") (class "Default")
      (node (ref "U17") (pin "8") (pinfunction "VCC_8") (pintype "bidirectional+no_connect"))
    )
    (net (code "82") (name "unconnected-(USB1-SBU1-Pad9)") (class "Default")
      (node (ref "USB1") (pin "9") (pinfunction "SBU1_9") (pintype "unspecified+no_connect"))
    )
    (net (code "83") (name "unconnected-(USB1-SBU2-Pad3)") (class "Default")
      (node (ref "USB1") (pin "3") (pinfunction "SBU2_3") (pintype "unspecified+no_connect"))
    )
  )
)
